# 11-multimodal-accelerometer.net
KiCad netlist of a schematic drawn in Altium Designer
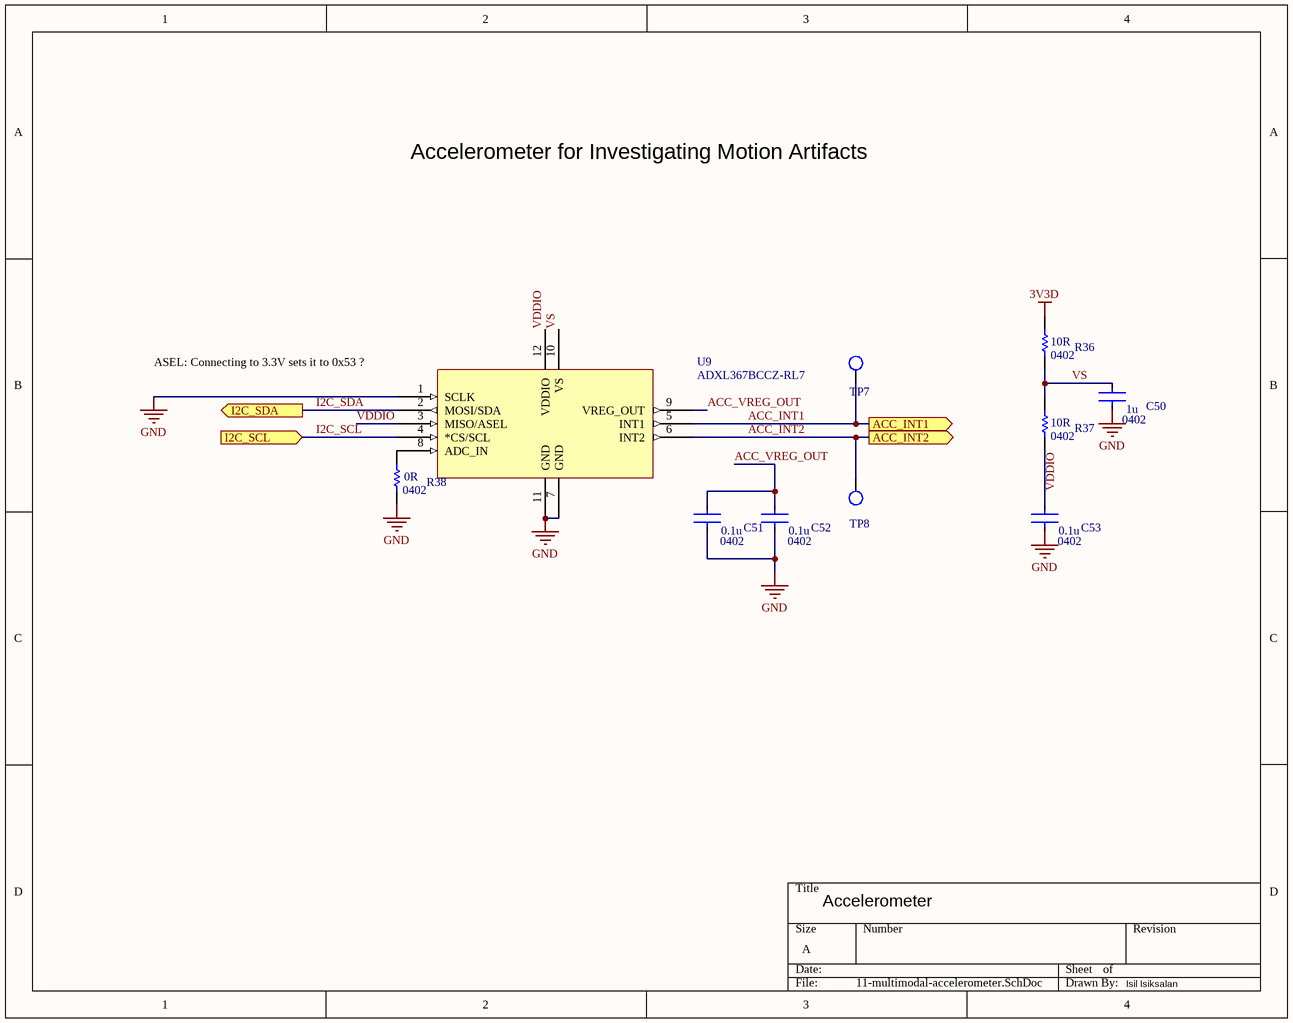
[diagram p0: 11-multimodal-accelerometer.SchDoc]

(export (version "E")
  (design (tool "Eeschema 10.0.6"))
  (components
    (comp (ref "C50")
      (value "C1005X5R1V105K050BC")
      (footprint "CAPTDK0402")
      (description "CAP CER 1UF 35V X5R 0402")
      (libsource (lib "multimodal") (part "C1005X5R1V105K050BC"))
    )
    (comp (ref "C51")
      (value "C1005X7R1H104K050BB")
      (footprint "CAPTDK0402")
      (description "CAP CER 0.1UF 50V X7R 0402")
      (libsource (lib "multimodal") (part "C1005X7R1H104K050BB"))
    )
    (comp (ref "C52")
      (value "C1005X7R1H104K050BB")
      (footprint "CAPTDK0402")
      (description "CAP CER 0.1UF 50V X7R 0402")
      (libsource (lib "multimodal") (part "C1005X7R1H104K050BB"))
    )
    (comp (ref "C53")
      (value "C1005X7R1H104K050BB")
      (footprint "CAPTDK0402")
      (description "CAP CER 0.1UF 50V X7R 0402")
      (libsource (lib "multimodal") (part "C1005X7R1H104K050BB"))
    )
    (comp (ref "R36")
      (value "RMCF0402FT10R0")
      (footprint "RES-STACK-POLE-0402")
      (description "RES 10 OHM 1% 1/16W 0402")
      (libsource (lib "multimodal") (part "RMCF0402FT10R0"))
    )
    (comp (ref "R37")
      (value "RMCF0402FT10R0")
      (footprint "RES-STACK-POLE-0402")
      (description "RES 10 OHM 1% 1/16W 0402")
      (libsource (lib "multimodal") (part "RMCF0402FT10R0"))
    )
    (comp (ref "R38")
      (value "RMCF0402ZT0R00")
      (footprint "RES-STACK-POLE-0402")
      (description "RES 0 OHM JUMPER 1/16W 0402")
      (libsource (lib "multimodal") (part "RMCF0402ZT0R00"))
    )
    (comp (ref "TP7")
      (value "TESTPOINT_S")
      (footprint "TESTPOINT_S")
      (description "Testpoint Surface Pad")
      (libsource (lib "multimodal") (part "TESTPOINT_S"))
    )
    (comp (ref "TP8")
      (value "TESTPOINT_S")
      (footprint "TESTPOINT_S")
      (description "Testpoint Surface Pad")
      (libsource (lib "multimodal") (part "TESTPOINT_S"))
    )
    (comp (ref "U9")
      (value "ADXL367BCCZ-RL7")
      (footprint "ADXL367BCCZ-RL7")
      (description "Accelerometer X, Y, Z Axis ±2g, 4g, 8g 6.25Hz ~ 200Hz 12-LGA (2.2x2.3)")
      (fields (field (name "COPYRIGHT") "Copyright (C) 2025 Ultra Librarian. All rights reserved."))
      (libsource (lib "multimodal") (part "ADXL367BCCZ-RL7"))
    )
  )
  (nets
    (net (code "1") (name "/ACC_INT1") (class "Default")
      (node (ref "TP7") (pin "1") (pinfunction "1_1") (pintype "passive"))
      (node (ref "U9") (pin "5") (pinfunction "INT1_5") (pintype "output"))
    )
    (net (code "2") (name "/ACC_INT2") (class "Default")
      (node (ref "TP8") (pin "1") (pinfunction "1_1") (pintype "passive"))
      (node (ref "U9") (pin "6") (pinfunction "INT2_6") (pintype "output"))
    )
    (net (code "3") (name "/ACC_VREG_OUT") (class "Default")
      (node (ref "C51") (pin "1") (pinfunction "1_1") (pintype "passive"))
      (node (ref "C52") (pin "1") (pinfunction "1_1") (pintype "passive"))
      (node (ref "U9") (pin "9") (pinfunction "VREG_OUT_9") (pintype "output"))
    )
    (net (code "4") (name "/I2C_SCL") (class "Default")
      (node (ref "U9") (pin "4") (pinfunction "*CS/SCL_4") (pintype "input"))
    )
    (net (code "5") (name "/I2C_SDA") (class "Default")
      (node (ref "U9") (pin "2") (pinfunction "MOSI/SDA_2") (pintype "output"))
    )
    (net (code "6") (name "/VDDIO") (class "Default")
      (node (ref "U9") (pin "12") (pinfunction "VDDIO_12") (pintype "power_in"))
      (node (ref "U9") (pin "3") (pinfunction "MISO/ASEL_3") (pintype "input"))
    )
    (net (code "7") (name "/VS") (class "Default")
      (node (ref "C50") (pin "1") (pinfunction "1_1") (pintype "passive"))
      (node (ref "R36") (pin "1") (pinfunction "1_1") (pintype "passive"))
      (node (ref "R37") (pin "2") (pinfunction "2_2") (pintype "passive"))
      (node (ref "U9") (pin "10") (pinfunction "VS_10") (pintype "power_in"))
    )
    (net (code "8") (name "3V3D") (class "Default")
      (node (ref "R36") (pin "2") (pinfunction "2_2") (pintype "passive"))
    )
    (net (code "9") (name "GND") (class "Default")
      (node (ref "C50") (pin "2") (pinfunction "2_2") (pintype "passive"))
      (node (ref "C51") (pin "2") (pinfunction "2_2") (pintype "passive"))
      (node (ref "C52") (pin "2") (pinfunction "2_2") (pintype "passive"))
      (node (ref "C53") (pin "2") (pinfunction "2_2") (pintype "passive"))
      (node (ref "R38") (pin "1") (pinfunction "1_1") (pintype "passive"))
      (node (ref "U9") (pin "1") (pinfunction "SCLK_1") (pintype "input"))
      (node (ref "U9") (pin "11") (pinfunction "GND_11") (pintype "power_in"))
      (node (ref "U9") (pin "7") (pinfunction "GND_7") (pintype "power_in"))
    )
    (net (code "10") (name "Net-(C53-Pad1)") (class "Default")
      (node (ref "C53") (pin "1") (pinfunction "1_1") (pintype "passive"))
      (node (ref "R37") (pin "1") (pinfunction "1_1") (pintype "passive"))
    )
    (net (code "11") (name "Net-(U9-ADC_IN)") (class "Default")
      (node (ref "R38") (pin "2") (pinfunction "2_2") (pintype "passive"))
      (node (ref "U9") (pin "8") (pinfunction "ADC_IN_8") (pintype "input"))
    )
  )
)
